# working.net
KiCad netlist of a schematic drawn in EAGLE
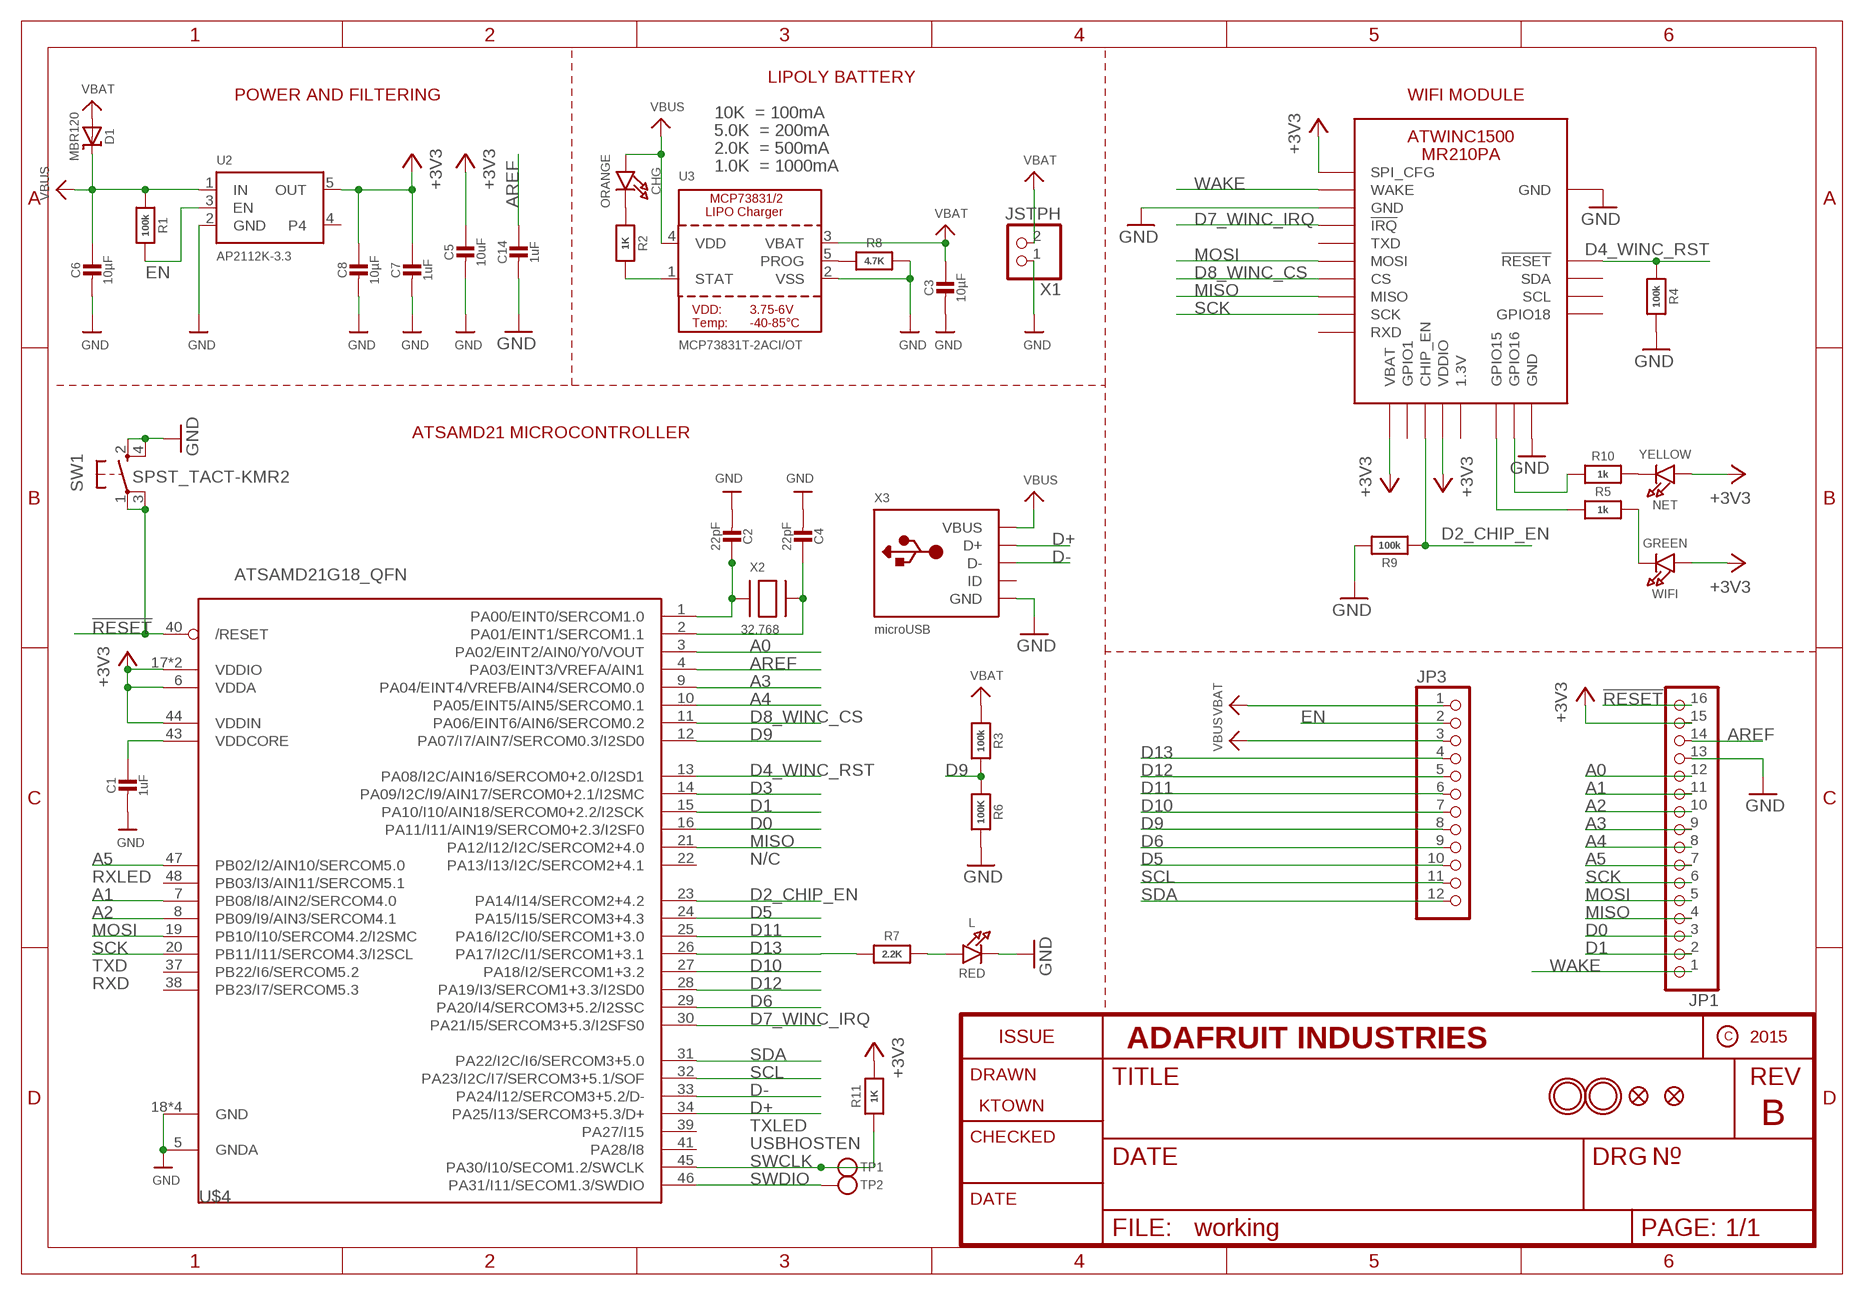
[diagram p0: schematic, sheet 1]

(export (version "E")
  (design (tool "Eeschema 10.0.6"))
  (components
    (comp (ref "C1")
      (value "1uF")
      (footprint "eagle-import:0603-NO")
      (libsource (lib "eagle-import") (part "CAP_CERAMIC0603_NO"))
    )
    (comp (ref "C2")
      (value "22pF")
      (footprint "eagle-import:0603-NO")
      (libsource (lib "eagle-import") (part "CAP_CERAMIC0603_NO"))
    )
    (comp (ref "C3")
      (value "10µF")
      (footprint "eagle-import:0805-NO")
      (libsource (lib "eagle-import") (part "CAP_CERAMIC0805-NOOUTLINE"))
    )
    (comp (ref "C4")
      (value "22pF")
      (footprint "eagle-import:0603-NO")
      (libsource (lib "eagle-import") (part "CAP_CERAMIC0603_NO"))
    )
    (comp (ref "C5")
      (value "10uF")
      (footprint "eagle-import:0805-NO")
      (libsource (lib "eagle-import") (part "CAP_CERAMIC0805-NOOUTLINE"))
    )
    (comp (ref "C6")
      (value "10µF")
      (footprint "eagle-import:0805-NO")
      (libsource (lib "eagle-import") (part "CAP_CERAMIC0805-NOOUTLINE"))
    )
    (comp (ref "C7")
      (value "1uF")
      (footprint "eagle-import:0603-NO")
      (libsource (lib "eagle-import") (part "CAP_CERAMIC0603_NO"))
    )
    (comp (ref "C8")
      (value "10µF")
      (footprint "eagle-import:0805-NO")
      (libsource (lib "eagle-import") (part "CAP_CERAMIC0805-NOOUTLINE"))
    )
    (comp (ref "C14")
      (value "1uF")
      (footprint "eagle-import:0603-NO")
      (libsource (lib "eagle-import") (part "CAP_CERAMIC0603_NO"))
    )
    (comp (ref "CHG")
      (value "ORANGE")
      (footprint "eagle-import:CHIPLED_0805_NOOUTLINE")
      (libsource (lib "eagle-import") (part "LED0805_NOOUTLINE"))
    )
    (comp (ref "D1")
      (value "MBR120")
      (footprint "eagle-import:SOD-123")
      (libsource (lib "eagle-import") (part "DIODE-SCHOTTKYSOD-123"))
    )
    (comp (ref "JP1")
      (value "HEADER-1X16ROUND")
      (footprint "eagle-import:1X16_ROUND")
      (libsource (lib "eagle-import") (part "HEADER-1X16ROUND"))
    )
    (comp (ref "JP3")
      (value "HEADER-1X12")
      (footprint "eagle-import:1X12_ROUND")
      (libsource (lib "eagle-import") (part "HEADER-1X12"))
    )
    (comp (ref "L")
      (value "RED")
      (footprint "eagle-import:CHIPLED_0805_NOOUTLINE")
      (libsource (lib "eagle-import") (part "LED0805_NOOUTLINE"))
    )
    (comp (ref "NET")
      (value "YELLOW")
      (footprint "eagle-import:CHIPLED_0805_NOOUTLINE")
      (libsource (lib "eagle-import") (part "LED0805_NOOUTLINE"))
    )
    (comp (ref "R1")
      (value "100k")
      (footprint "eagle-import:0603-NO")
      (libsource (lib "eagle-import") (part "RESISTOR_0603_NOOUT"))
    )
    (comp (ref "R2")
      (value "1K")
      (footprint "eagle-import:0603-NO")
      (libsource (lib "eagle-import") (part "RESISTOR_0603_NOOUT"))
    )
    (comp (ref "R3")
      (value "100k")
      (footprint "eagle-import:0603-NO")
      (libsource (lib "eagle-import") (part "RESISTOR_0603_NOOUT"))
    )
    (comp (ref "R4")
      (value "100k")
      (footprint "eagle-import:0603-NO")
      (libsource (lib "eagle-import") (part "RESISTOR_0603_NOOUT"))
    )
    (comp (ref "R5")
      (value "1k")
      (footprint "eagle-import:0603-NO")
      (libsource (lib "eagle-import") (part "RESISTOR_0603_NOOUT"))
    )
    (comp (ref "R6")
      (value "100K")
      (footprint "eagle-import:0603-NO")
      (libsource (lib "eagle-import") (part "RESISTOR_0603_NOOUT"))
    )
    (comp (ref "R7")
      (value "2.2K")
      (footprint "eagle-import:0603-NO")
      (libsource (lib "eagle-import") (part "RESISTOR_0603_NOOUT"))
    )
    (comp (ref "R8")
      (value "4.7K")
      (footprint "eagle-import:0603-NO")
      (libsource (lib "eagle-import") (part "RESISTOR_0603_NOOUT"))
    )
    (comp (ref "R9")
      (value "100k")
      (footprint "eagle-import:0603-NO")
      (libsource (lib "eagle-import") (part "RESISTOR_0603_NOOUT"))
    )
    (comp (ref "R10")
      (value "1k")
      (footprint "eagle-import:0603-NO")
      (libsource (lib "eagle-import") (part "RESISTOR_0603_NOOUT"))
    )
    (comp (ref "R11")
      (value "1K")
      (footprint "eagle-import:0603-NO")
      (libsource (lib "eagle-import") (part "RESISTOR_0603_NOOUT"))
    )
    (comp (ref "SW1")
      (value "SPST_TACT-KMR2")
      (footprint "eagle-import:KMR2")
      (libsource (lib "eagle-import") (part "SPST_TACT-KMR2"))
    )
    (comp (ref "TP1")
      (value "TESTPOINTROUND1.5MM")
      (footprint "eagle-import:TESTPOINT_ROUND_1.5MM")
      (libsource (lib "eagle-import") (part "TESTPOINTROUND1.5MM"))
    )
    (comp (ref "TP2")
      (value "TESTPOINTROUND1.5MM")
      (footprint "eagle-import:TESTPOINT_ROUND_1.5MM")
      (libsource (lib "eagle-import") (part "TESTPOINTROUND1.5MM"))
    )
    (comp (ref "U$4")
      (value "ATSAMD21G18_QFN")
      (footprint "eagle-import:TQFN48_7MM")
      (libsource (lib "eagle-import") (part "ATSAMD21J_QFN"))
    )
    (comp (ref "U$31")
      (value "MOUNTINGHOLE2.5")
      (footprint "eagle-import:MOUNTINGHOLE_2.5_PLATED")
      (libsource (lib "eagle-import") (part "MOUNTINGHOLE2.5"))
    )
    (comp (ref "U$32")
      (value "MOUNTINGHOLE2.5")
      (footprint "eagle-import:MOUNTINGHOLE_2.5_PLATED")
      (libsource (lib "eagle-import") (part "MOUNTINGHOLE2.5"))
    )
    (comp (ref "U$34")
      (value "FIDUCIAL\"\"")
      (footprint "eagle-import:FIDUCIAL_1MM")
      (libsource (lib "eagle-import") (part "FIDUCIAL{dblquote}{dblquote}"))
    )
    (comp (ref "U$35")
      (value "FIDUCIAL\"\"")
      (footprint "eagle-import:FIDUCIAL_1MM")
      (libsource (lib "eagle-import") (part "FIDUCIAL{dblquote}{dblquote}"))
    )
    (comp (ref "U2")
      (value "AP2112K-3.3")
      (footprint "eagle-import:SOT23-5")
      (libsource (lib "eagle-import") (part "VREG_SOT23-5"))
    )
    (comp (ref "U3")
      (value "MCP73831T-2ACI/OT")
      (footprint "eagle-import:SOT23-5")
      (libsource (lib "eagle-import") (part "MCP73831/2"))
    )
    (comp (ref "WIFI")
      (value "GREEN")
      (footprint "eagle-import:CHIPLED_0805_NOOUTLINE")
      (libsource (lib "eagle-import") (part "LED0805_NOOUTLINE"))
    )
    (comp (ref "X1")
      (value "JSTPH")
      (footprint "eagle-import:JSTPH2")
      (libsource (lib "eagle-import") (part "CON_JST_PH_2PIN"))
    )
    (comp (ref "X2")
      (value "32.768")
      (footprint "eagle-import:XTAL3215")
      (libsource (lib "eagle-import") (part "XTAL-3.2X1.5"))
    )
    (comp (ref "X3")
      (value "microUSB")
      (footprint "eagle-import:4UCONN_20329_V2")
      (libsource (lib "eagle-import") (part "USB_MICRO_20329_V2"))
    )
    (comp (ref "X4")
      (value "ATWINC1500_MR210PA")
      (footprint "eagle-import:ATWINC1500_MR210PA")
      (libsource (lib "eagle-import") (part "ATWINC1500_MR210PA"))
    )
  )
  (nets
    (net (code "1") (name "+3V3") (class "Default")
      (node (ref "C5") (pin "1") (pinfunction "1_1") (pintype "passive"))
      (node (ref "C7") (pin "1") (pinfunction "1_1") (pintype "passive"))
      (node (ref "C8") (pin "1") (pinfunction "1_1") (pintype "passive"))
      (node (ref "JP1") (pin "15") (pinfunction "15_15") (pintype "passive"))
      (node (ref "NET") (pin "A") (pinfunction "A_A") (pintype "passive"))
      (node (ref "R11") (pin "2") (pinfunction "2_2") (pintype "passive"))
      (node (ref "U$4") (pin "17") (pinfunction "VDDIO_17") (pintype "power_in"))
      (node (ref "U$4") (pin "36") (pinfunction "VDDIO_36") (pintype "power_in"))
      (node (ref "U$4") (pin "44") (pinfunction "VDDIN_44") (pintype "power_in"))
      (node (ref "U$4") (pin "6") (pinfunction "VDDA_6") (pintype "power_in"))
      (node (ref "U2") (pin "5") (pinfunction "OUT_5") (pintype "power_in"))
      (node (ref "WIFI") (pin "A") (pinfunction "A_A") (pintype "passive"))
      (node (ref "X4") (pin "J10") (pinfunction "SPI_CFG_J10") (pintype "input"))
      (node (ref "X4") (pin "J20") (pinfunction "VBAT_J20") (pintype "power_in"))
      (node (ref "X4") (pin "J23") (pinfunction "VDDIO_J23") (pintype "power_in"))
    )
    (net (code "2") (name "/A0") (class "Default")
      (node (ref "JP1") (pin "12") (pinfunction "12_12") (pintype "passive"))
      (node (ref "U$4") (pin "3") (pinfunction "PA02/EINT2/AIN0/Y0/VOUT_3") (pintype "bidirectional"))
    )
    (net (code "3") (name "/A1") (class "Default")
      (node (ref "JP1") (pin "11") (pinfunction "11_11") (pintype "passive"))
      (node (ref "U$4") (pin "7") (pinfunction "PB08/I8/AIN2/SERCOM4.0_7") (pintype "bidirectional"))
    )
    (net (code "4") (name "/A2") (class "Default")
      (node (ref "JP1") (pin "10") (pinfunction "10_10") (pintype "passive"))
      (node (ref "U$4") (pin "8") (pinfunction "PB09/I9/AIN3/SERCOM4.1_8") (pintype "bidirectional"))
    )
    (net (code "5") (name "/A3") (class "Default")
      (node (ref "JP1") (pin "9") (pinfunction "9_9") (pintype "passive"))
      (node (ref "U$4") (pin "9") (pinfunction "PA04/EINT4/VREFB/AIN4/SERCOM0.0_9") (pintype "bidirectional"))
    )
    (net (code "6") (name "/A4") (class "Default")
      (node (ref "JP1") (pin "8") (pinfunction "8_8") (pintype "passive"))
      (node (ref "U$4") (pin "10") (pinfunction "PA05/EINT5/AIN5/SERCOM0.1_10") (pintype "bidirectional"))
    )
    (net (code "7") (name "/A5") (class "Default")
      (node (ref "JP1") (pin "7") (pinfunction "7_7") (pintype "passive"))
      (node (ref "U$4") (pin "47") (pinfunction "PB02/I2/AIN10/SERCOM5.0_47") (pintype "bidirectional"))
    )
    (net (code "8") (name "/AREF") (class "Default")
      (node (ref "C14") (pin "1") (pinfunction "1_1") (pintype "passive"))
      (node (ref "JP1") (pin "14") (pinfunction "14_14") (pintype "passive"))
      (node (ref "U$4") (pin "4") (pinfunction "PA03/EINT3/VREFA/AIN1_4") (pintype "bidirectional"))
    )
    (net (code "9") (name "/D+") (class "Default")
      (node (ref "U$4") (pin "34") (pinfunction "PA25/I13/SERCOM3+5.3/D+_34") (pintype "bidirectional"))
      (node (ref "X3") (pin "D+") (pinfunction "D+_D+") (pintype "bidirectional"))
    )
    (net (code "10") (name "/D-") (class "Default")
      (node (ref "U$4") (pin "33") (pinfunction "PA24/I12/SERCOM3+5.2/D-_33") (pintype "bidirectional"))
      (node (ref "X3") (pin "D-") (pinfunction "D-_D-") (pintype "bidirectional"))
    )
    (net (code "11") (name "/D0") (class "Default")
      (node (ref "JP1") (pin "3") (pinfunction "3_3") (pintype "passive"))
      (node (ref "U$4") (pin "16") (pinfunction "PA11/I11/AIN19/SERCOM0+2.3/I2SF0_16") (pintype "bidirectional"))
    )
    (net (code "12") (name "/D1") (class "Default")
      (node (ref "JP1") (pin "2") (pinfunction "2_2") (pintype "passive"))
      (node (ref "U$4") (pin "15") (pinfunction "PA10/I10/AIN18/SERCOM0+2.2/I2SCK_15") (pintype "bidirectional"))
    )
    (net (code "13") (name "/D2_CHIP_EN") (class "Default")
      (node (ref "R9") (pin "1") (pinfunction "1_1") (pintype "passive"))
      (node (ref "U$4") (pin "23") (pinfunction "PA14/I14/SERCOM2+4.2_23") (pintype "bidirectional"))
      (node (ref "X4") (pin "J22") (pinfunction "CHIP_EN_J22") (pintype "input"))
    )
    (net (code "14") (name "/D3") (class "Default")
      (node (ref "U$4") (pin "14") (pinfunction "PA09/I2C/I9/AIN17/SERCOM0+2.1/I2SMC_14") (pintype "bidirectional"))
    )
    (net (code "15") (name "/D4_WINC_RST") (class "Default")
      (node (ref "R4") (pin "1") (pinfunction "1_1") (pintype "passive"))
      (node (ref "U$4") (pin "13") (pinfunction "PA08/I2C/AIN16/SERCOM0+2.0/I2SD1_13") (pintype "bidirectional"))
      (node (ref "X4") (pin "J4") (pinfunction "~{RESET}_J4") (pintype "input"))
    )
    (net (code "16") (name "/D5") (class "Default")
      (node (ref "JP3") (pin "10") (pinfunction "10_10") (pintype "passive"))
      (node (ref "U$4") (pin "24") (pinfunction "PA15/I15/SERCOM3+4.3_24") (pintype "bidirectional"))
    )
    (net (code "17") (name "/D6") (class "Default")
      (node (ref "JP3") (pin "9") (pinfunction "9_9") (pintype "passive"))
      (node (ref "U$4") (pin "29") (pinfunction "PA20/I4/SERCOM3+5.2/I2SSC_29") (pintype "bidirectional"))
    )
    (net (code "18") (name "/D7_WINC_IRQ") (class "Default")
      (node (ref "U$4") (pin "30") (pinfunction "PA21/I5/SERCOM3+5.3/I2SFS0_30") (pintype "bidirectional"))
      (node (ref "X4") (pin "J13") (pinfunction "~{IRQ}_J13") (pintype "output"))
    )
    (net (code "19") (name "/D8_WINC_CS") (class "Default")
      (node (ref "U$4") (pin "11") (pinfunction "PA06/EINT6/AIN6/SERCOM0.2_11") (pintype "bidirectional"))
      (node (ref "X4") (pin "J16") (pinfunction "CS_J16") (pintype "input"))
    )
    (net (code "20") (name "/D9") (class "Default")
      (node (ref "JP3") (pin "8") (pinfunction "8_8") (pintype "passive"))
      (node (ref "R3") (pin "2") (pinfunction "2_2") (pintype "passive"))
      (node (ref "R6") (pin "1") (pinfunction "1_1") (pintype "passive"))
      (node (ref "U$4") (pin "12") (pinfunction "PA07/I7/AIN7/SERCOM0.3/I2SD0_12") (pintype "bidirectional"))
    )
    (net (code "21") (name "/D10") (class "Default")
      (node (ref "JP3") (pin "7") (pinfunction "7_7") (pintype "passive"))
      (node (ref "U$4") (pin "27") (pinfunction "PA18/I2/SERCOM1+3.2_27") (pintype "bidirectional"))
    )
    (net (code "22") (name "/D11") (class "Default")
      (node (ref "JP3") (pin "6") (pinfunction "6_6") (pintype "passive"))
      (node (ref "U$4") (pin "25") (pinfunction "PA16/I2C/I0/SERCOM1+3.0_25") (pintype "bidirectional"))
    )
    (net (code "23") (name "/D12") (class "Default")
      (node (ref "JP3") (pin "5") (pinfunction "5_5") (pintype "passive"))
      (node (ref "U$4") (pin "28") (pinfunction "PA19/I3/SERCOM1+3.3/I2SD0_28") (pintype "bidirectional"))
    )
    (net (code "24") (name "/D13") (class "Default")
      (node (ref "JP3") (pin "4") (pinfunction "4_4") (pintype "passive"))
      (node (ref "R7") (pin "1") (pinfunction "1_1") (pintype "passive"))
      (node (ref "U$4") (pin "26") (pinfunction "PA17/I2C/I1/SERCOM1+3.1_26") (pintype "bidirectional"))
    )
    (net (code "25") (name "/EN") (class "Default")
      (node (ref "JP3") (pin "2") (pinfunction "2_2") (pintype "passive"))
      (node (ref "R1") (pin "2") (pinfunction "2_2") (pintype "passive"))
      (node (ref "U2") (pin "3") (pinfunction "EN_3") (pintype "input"))
    )
    (net (code "26") (name "/MISO") (class "Default")
      (node (ref "JP1") (pin "4") (pinfunction "4_4") (pintype "passive"))
      (node (ref "U$4") (pin "21") (pinfunction "PA12/I12/I2C/SERCOM2+4.0_21") (pintype "bidirectional"))
      (node (ref "X4") (pin "J17") (pinfunction "MISO_J17") (pintype "output"))
    )
    (net (code "27") (name "/MOSI") (class "Default")
      (node (ref "JP1") (pin "5") (pinfunction "5_5") (pintype "passive"))
      (node (ref "U$4") (pin "19") (pinfunction "PB10/I10/SERCOM4.2/I2SMC_19") (pintype "bidirectional"))
      (node (ref "X4") (pin "J15") (pinfunction "MOSI_J15") (pintype "input"))
    )
    (net (code "28") (name "/SCK") (class "Default")
      (node (ref "JP1") (pin "6") (pinfunction "6_6") (pintype "passive"))
      (node (ref "U$4") (pin "20") (pinfunction "PB11/I11/SERCOM4.3/I2SCL_20") (pintype "bidirectional"))
      (node (ref "X4") (pin "J18") (pinfunction "SCK_J18") (pintype "input"))
    )
    (net (code "29") (name "/SCL") (class "Default")
      (node (ref "JP3") (pin "11") (pinfunction "11_11") (pintype "passive"))
      (node (ref "U$4") (pin "32") (pinfunction "PA23/I2C/I7/SERCOM3+5.1/SOF_32") (pintype "bidirectional"))
    )
    (net (code "30") (name "/SDA") (class "Default")
      (node (ref "JP3") (pin "12") (pinfunction "12_12") (pintype "passive"))
      (node (ref "U$4") (pin "31") (pinfunction "PA22/I2C/I6/SERCOM3+5.0_31") (pintype "bidirectional"))
    )
    (net (code "31") (name "/SWCLK") (class "Default")
      (node (ref "R11") (pin "1") (pinfunction "1_1") (pintype "passive"))
      (node (ref "TP1") (pin "P$1") (pinfunction "P$1_P$1") (pintype "bidirectional"))
      (node (ref "U$4") (pin "45") (pinfunction "PA30/I10/SECOM1.2/SWCLK_45") (pintype "bidirectional"))
    )
    (net (code "32") (name "/SWDIO") (class "Default")
      (node (ref "TP2") (pin "P$1") (pinfunction "P$1_P$1") (pintype "bidirectional"))
      (node (ref "U$4") (pin "46") (pinfunction "PA31/I11/SECOM1.3/SWDIO_46") (pintype "bidirectional"))
    )
    (net (code "33") (name "/WAKE") (class "Default")
      (node (ref "JP1") (pin "1") (pinfunction "1_1") (pintype "passive"))
      (node (ref "X4") (pin "J11") (pinfunction "WAKE_J11") (pintype "input"))
    )
    (net (code "34") (name "/~{RESET}") (class "Default")
      (node (ref "JP1") (pin "16") (pinfunction "16_16") (pintype "passive"))
      (node (ref "SW1") (pin "1") (pinfunction "P_1") (pintype "passive"))
      (node (ref "SW1") (pin "3") (pinfunction "P1_3") (pintype "passive"))
      (node (ref "U$4") (pin "40") (pinfunction "/RESET_40") (pintype "bidirectional"))
    )
    (net (code "35") (name "GND") (class "Default")
      (node (ref "C1") (pin "2") (pinfunction "2_2") (pintype "passive"))
      (node (ref "C14") (pin "2") (pinfunction "2_2") (pintype "passive"))
      (node (ref "C2") (pin "2") (pinfunction "2_2") (pintype "passive"))
      (node (ref "C3") (pin "2") (pinfunction "2_2") (pintype "passive"))
      (node (ref "C4") (pin "2") (pinfunction "2_2") (pintype "passive"))
      (node (ref "C5") (pin "2") (pinfunction "2_2") (pintype "passive"))
      (node (ref "C6") (pin "2") (pinfunction "2_2") (pintype "passive"))
      (node (ref "C7") (pin "2") (pinfunction "2_2") (pintype "passive"))
      (node (ref "C8") (pin "2") (pinfunction "2_2") (pintype "passive"))
      (node (ref "JP1") (pin "13") (pinfunction "13_13") (pintype "passive"))
      (node (ref "L") (pin "C") (pinfunction "C_C") (pintype "passive"))
      (node (ref "R4") (pin "2") (pinfunction "2_2") (pintype "passive"))
      (node (ref "R6") (pin "2") (pinfunction "2_2") (pintype "passive"))
      (node (ref "R8") (pin "2") (pinfunction "2_2") (pintype "passive"))
      (node (ref "R9") (pin "2") (pinfunction "2_2") (pintype "passive"))
      (node (ref "SW1") (pin "2") (pinfunction "S_2") (pintype "passive"))
      (node (ref "SW1") (pin "4") (pinfunction "S1_4") (pintype "passive"))
      (node (ref "U$4") (pin "18") (pinfunction "GND_18") (pintype "power_in"))
      (node (ref "U$4") (pin "35") (pinfunction "GND_35") (pintype "power_in"))
      (node (ref "U$4") (pin "42") (pinfunction "GND_42") (pintype "power_in"))
      (node (ref "U$4") (pin "5") (pinfunction "GNDA_5") (pintype "power_in"))
      (node (ref "U$4") (pin "THERMAL") (pinfunction "GND_THERMAL") (pintype "power_in"))
      (node (ref "U2") (pin "2") (pinfunction "GND_2") (pintype "power_in"))
      (node (ref "U3") (pin "2") (pinfunction "VSS_2") (pintype "power_in"))
      (node (ref "X1") (pin "1") (pinfunction "1_1") (pintype "passive"))
      (node (ref "X3") (pin "BASE@1") (pinfunction "GND_BASE@1") (pintype "power_in"))
      (node (ref "X3") (pin "BASE@2") (pinfunction "GND_BASE@2") (pintype "power_in"))
      (node (ref "X3") (pin "GND") (pinfunction "GND_GND") (pintype "power_in"))
      (node (ref "X3") (pin "SPRT@1") (pinfunction "GND_SPRT@1") (pintype "power_in"))
      (node (ref "X3") (pin "SPRT@2") (pinfunction "GND_SPRT@2") (pintype "power_in"))
      (node (ref "X3") (pin "SPRT@3") (pinfunction "GND_SPRT@3") (pintype "power_in"))
      (node (ref "X3") (pin "SPRT@4") (pinfunction "GND_SPRT@4") (pintype "power_in"))
      (node (ref "X4") (pin "J12") (pinfunction "GND_J12") (pintype "power_in"))
      (node (ref "X4") (pin "J28") (pinfunction "GND_J28") (pintype "power_in"))
      (node (ref "X4") (pin "J9") (pinfunction "GND_J9") (pintype "bidirectional"))
      (node (ref "X4") (pin "MTGND") (pinfunction "GND_MTGND") (pintype "power_in"))
    )
    (net (code "36") (name "Net-(CHG-PadC)") (class "Default")
      (node (ref "CHG") (pin "C") (pinfunction "C_C") (pintype "passive"))
      (node (ref "R2") (pin "1") (pinfunction "1_1") (pintype "passive"))
    )
    (net (code "37") (name "Net-(L-PadA)") (class "Default")
      (node (ref "L") (pin "A") (pinfunction "A_A") (pintype "passive"))
      (node (ref "R7") (pin "2") (pinfunction "2_2") (pintype "passive"))
    )
    (net (code "38") (name "Net-(NET-PadC)") (class "Default")
      (node (ref "NET") (pin "C") (pinfunction "C_C") (pintype "passive"))
      (node (ref "R10") (pin "2") (pinfunction "2_2") (pintype "passive"))
    )
    (net (code "39") (name "Net-(R5-Pad2)") (class "Default")
      (node (ref "R5") (pin "2") (pinfunction "2_2") (pintype "passive"))
      (node (ref "WIFI") (pin "C") (pinfunction "C_C") (pintype "passive"))
    )
    (net (code "40") (name "Net-(U$4-PA00{slash}EINT0{slash}SERCOM1.0)") (class "Default")
      (node (ref "C2") (pin "1") (pinfunction "1_1") (pintype "passive"))
      (node (ref "U$4") (pin "1") (pinfunction "PA00/EINT0/SERCOM1.0_1") (pintype "bidirectional"))
      (node (ref "X2") (pin "P$1") (pinfunction "P$1_P$1") (pintype "bidirectional"))
    )
    (net (code "41") (name "Net-(U$4-PA01{slash}EINT1{slash}SERCOM1.1)") (class "Default")
      (node (ref "C4") (pin "1") (pinfunction "1_1") (pintype "passive"))
      (node (ref "U$4") (pin "2") (pinfunction "PA01/EINT1/SERCOM1.1_2") (pintype "bidirectional"))
      (node (ref "X2") (pin "P$2") (pinfunction "P$2_P$2") (pintype "bidirectional"))
    )
    (net (code "42") (name "Net-(U$4-VDDCORE)") (class "Default")
      (node (ref "C1") (pin "1") (pinfunction "1_1") (pintype "passive"))
      (node (ref "U$4") (pin "43") (pinfunction "VDDCORE_43") (pintype "power_in"))
    )
    (net (code "43") (name "Net-(U3-PROG)") (class "Default")
      (node (ref "R8") (pin "1") (pinfunction "1_1") (pintype "passive"))
      (node (ref "U3") (pin "5") (pinfunction "PROG_5") (pintype "input"))
    )
    (net (code "44") (name "Net-(U3-STAT)") (class "Default")
      (node (ref "R2") (pin "2") (pinfunction "2_2") (pintype "passive"))
      (node (ref "U3") (pin "1") (pinfunction "STAT_1") (pintype "output"))
    )
    (net (code "45") (name "Net-(X4-GPIO15)") (class "Default")
      (node (ref "R5") (pin "1") (pinfunction "1_1") (pintype "passive"))
      (node (ref "X4") (pin "J26") (pinfunction "GPIO15_J26") (pintype "bidirectional"))
    )
    (net (code "46") (name "Net-(X4-GPIO16)") (class "Default")
      (node (ref "R10") (pin "1") (pinfunction "1_1") (pintype "passive"))
      (node (ref "X4") (pin "J27") (pinfunction "GPIO16_J27") (pintype "bidirectional"))
    )
    (net (code "47") (name "VBAT") (class "Default")
      (node (ref "C3") (pin "1") (pinfunction "1_1") (pintype "passive"))
      (node (ref "D1") (pin "A") (pinfunction "A_A") (pintype "passive"))
      (node (ref "JP3") (pin "1") (pinfunction "1_1") (pintype "passive"))
      (node (ref "R3") (pin "1") (pinfunction "1_1") (pintype "passive"))
      (node (ref "U3") (pin "3") (pinfunction "VBAT_3") (pintype "power_in"))
      (node (ref "X1") (pin "2") (pinfunction "2_2") (pintype "passive"))
    )
    (net (code "48") (name "VBUS") (class "Default")
      (node (ref "C6") (pin "1") (pinfunction "1_1") (pintype "passive"))
      (node (ref "CHG") (pin "A") (pinfunction "A_A") (pintype "passive"))
      (node (ref "D1") (pin "C") (pinfunction "C_C") (pintype "passive"))
      (node (ref "JP3") (pin "3") (pinfunction "3_3") (pintype "passive"))
      (node (ref "R1") (pin "1") (pinfunction "1_1") (pintype "passive"))
      (node (ref "U2") (pin "1") (pinfunction "IN_1") (pintype "power_in"))
      (node (ref "U3") (pin "4") (pinfunction "VDD_4") (pintype "power_in"))
      (node (ref "X3") (pin "VBUS") (pinfunction "VBUS_VBUS") (pintype "power_in"))
    )
    (net (code "49") (name "unconnected-(U$4-PA13{slash}I13{slash}I2C{slash}SERCOM2+4.1-Pad22)") (class "Default")
      (node (ref "U$4") (pin "22") (pinfunction "PA13/I13/I2C/SERCOM2+4.1_22") (pintype "bidirectional"))
    )
    (net (code "50") (name "unconnected-(U$4-PA27{slash}I15-Pad39)") (class "Default")
      (node (ref "U$4") (pin "39") (pinfunction "PA27/I15_39") (pintype "bidirectional"))
    )
    (net (code "51") (name "unconnected-(U$4-PA28{slash}I8-Pad41)") (class "Default")
      (node (ref "U$4") (pin "41") (pinfunction "PA28/I8_41") (pintype "bidirectional"))
    )
    (net (code "52") (name "unconnected-(U$4-PB03{slash}I3{slash}AIN11{slash}SERCOM5.1-Pad48)") (class "Default")
      (node (ref "U$4") (pin "48") (pinfunction "PB03/I3/AIN11/SERCOM5.1_48") (pintype "bidirectional"))
    )
    (net (code "53") (name "unconnected-(U$4-PB22{slash}I6{slash}SERCOM5.2-Pad37)") (class "Default")
      (node (ref "U$4") (pin "37") (pinfunction "PB22/I6/SERCOM5.2_37") (pintype "bidirectional"))
    )
    (net (code "54") (name "unconnected-(U$4-PB23{slash}I7{slash}SERCOM5.3-Pad38)") (class "Default")
      (node (ref "U$4") (pin "38") (pinfunction "PB23/I7/SERCOM5.3_38") (pintype "bidirectional"))
    )
    (net (code "55") (name "unconnected-(U2-P4-Pad4)") (class "Default")
      (node (ref "U2") (pin "4") (pinfunction "P4_4") (pintype "bidirectional"))
    )
    (net (code "56") (name "unconnected-(X3-PadID)") (class "Default")
      (node (ref "X3") (pin "ID") (pinfunction "ID_ID") (pintype "bidirectional"))
    )
    (net (code "57") (name "unconnected-(X4-1.3V-PadJ24)") (class "Default")
      (node (ref "X4") (pin "J24") (pinfunction "1.3V_J24") (pintype "passive"))
    )
    (net (code "58") (name "unconnected-(X4-GPIO1-PadJ21)") (class "Default")
      (node (ref "X4") (pin "J21") (pinfunction "GPIO1_J21") (pintype "bidirectional"))
    )
    (net (code "59") (name "unconnected-(X4-GPIO18-PadJ1)") (class "Default")
      (node (ref "X4") (pin "J1") (pinfunction "GPIO18_J1") (pintype "bidirectional"))
    )
    (net (code "60") (name "unconnected-(X4-RXD-PadJ19)") (class "Default")
      (node (ref "X4") (pin "J19") (pinfunction "RXD_J19") (pintype "input"))
    )
    (net (code "61") (name "unconnected-(X4-SCL-PadJ2)") (class "Default")
      (node (ref "X4") (pin "J2") (pinfunction "SCL_J2") (pintype "bidirectional"))
    )
    (net (code "62") (name "unconnected-(X4-SDA-PadJ3)") (class "Default")
      (node (ref "X4") (pin "J3") (pinfunction "SDA_J3") (pintype "bidirectional"))
    )
    (net (code "63") (name "unconnected-(X4-TXD-PadJ14)") (class "Default")
      (node (ref "X4") (pin "J14") (pinfunction "TXD_J14") (pintype "output"))
    )
  )
)
